# Adafruit_ItsyBitsy_M0.net
KiCad netlist of a schematic drawn in EAGLE
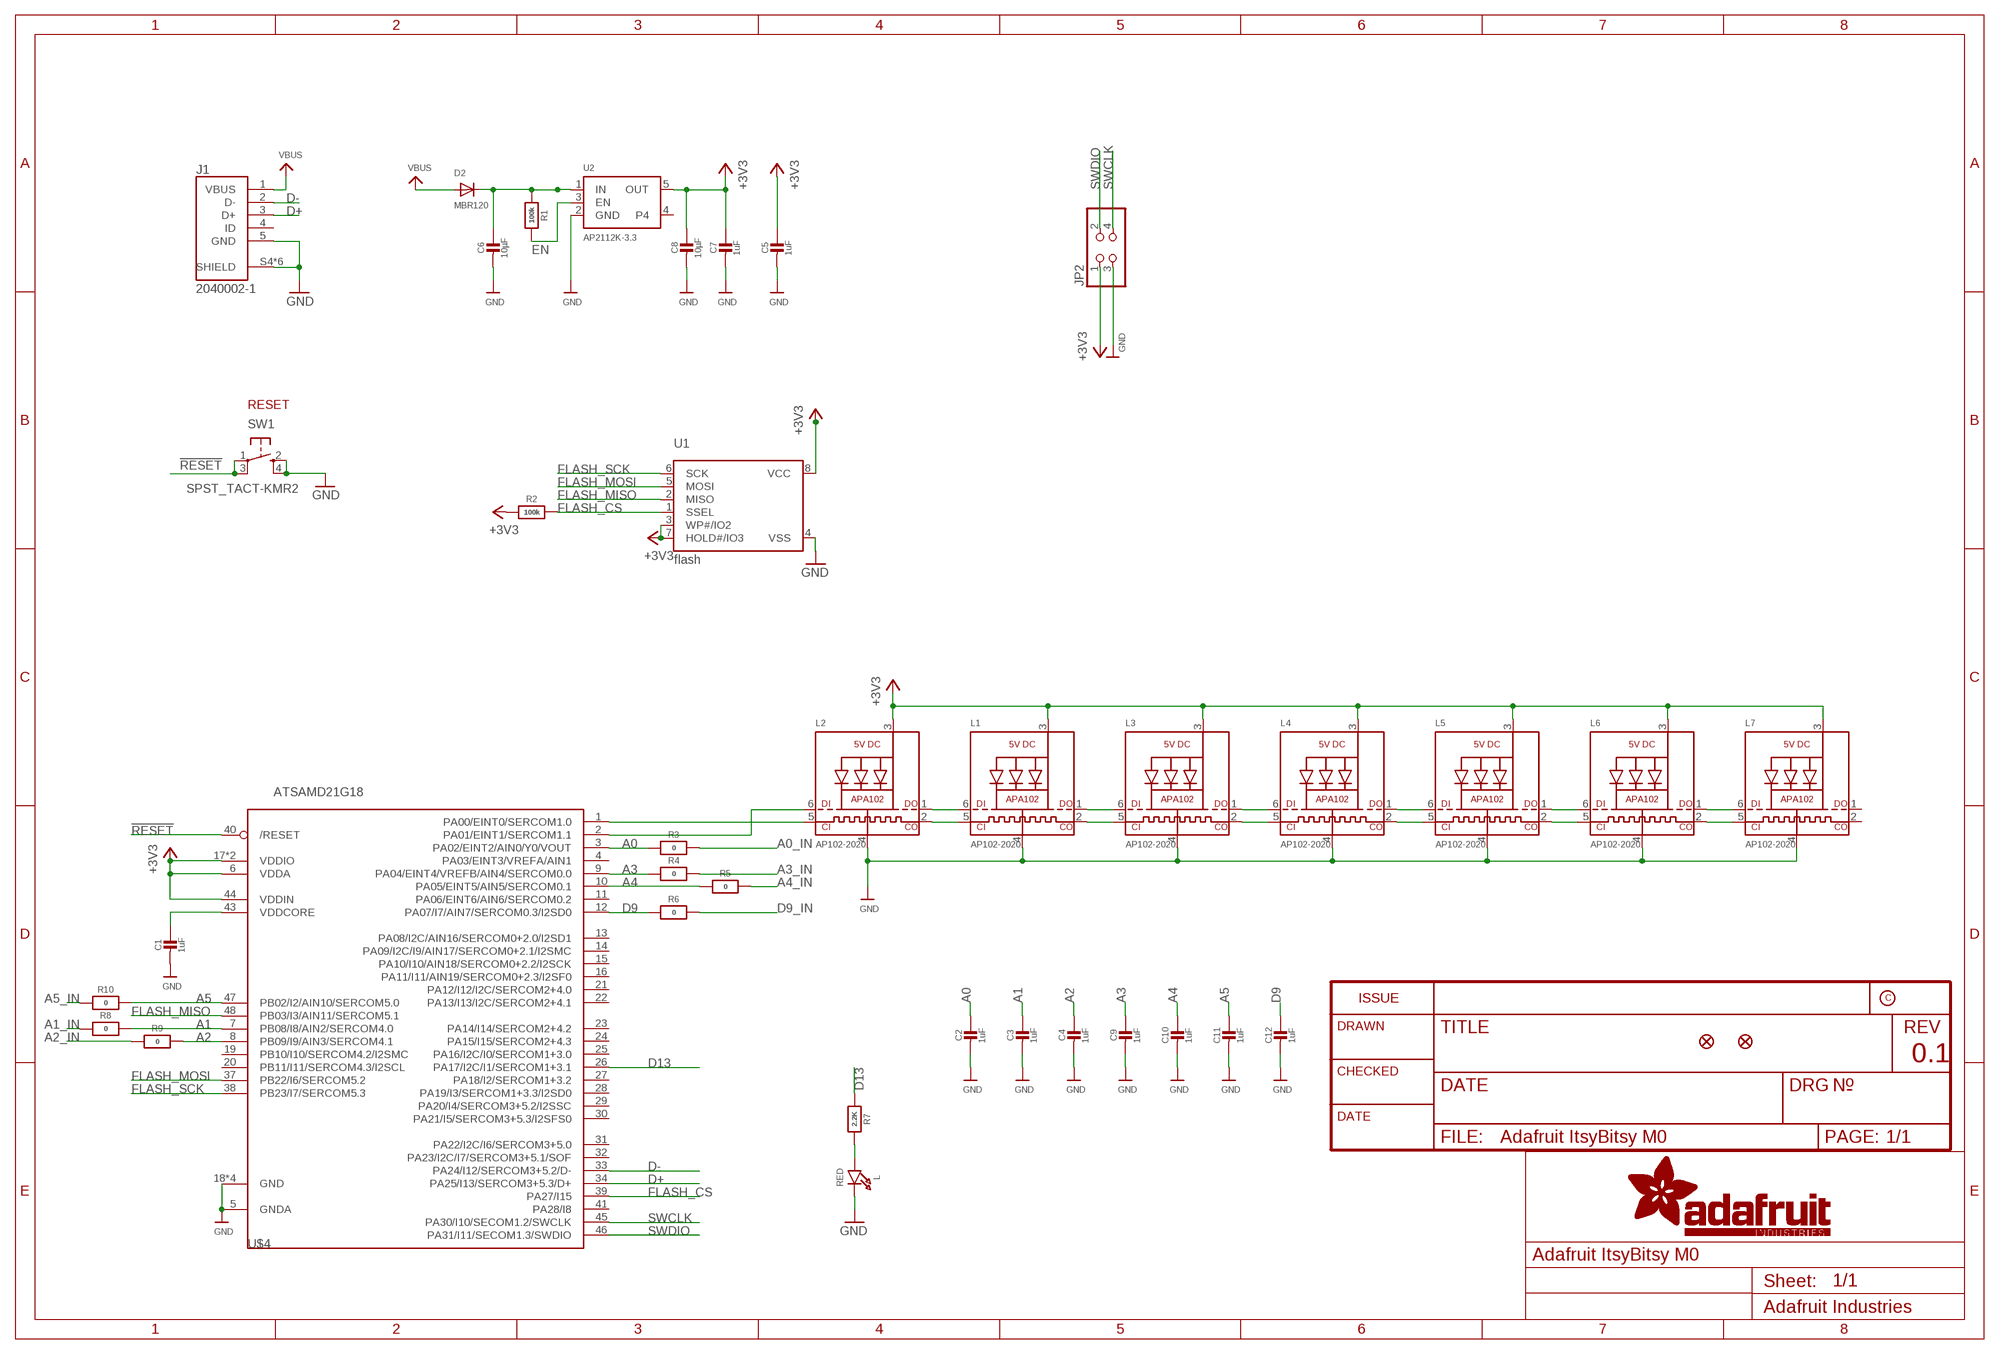
[diagram p0: schematic, sheet 1]

(export (version "E")
  (design (tool "Eeschema 10.0.6"))
  (components
    (comp (ref "C1")
      (value "1uF")
      (footprint "eagle-import:0603-NO")
      (libsource (lib "eagle-import") (part "CAP_CERAMIC0603_NO"))
    )
    (comp (ref "C2")
      (value "1uF")
      (footprint "eagle-import:0603-NO")
      (libsource (lib "eagle-import") (part "CAP_CERAMIC0603_NO"))
    )
    (comp (ref "C3")
      (value "1uF")
      (footprint "eagle-import:0603-NO")
      (libsource (lib "eagle-import") (part "CAP_CERAMIC0603_NO"))
    )
    (comp (ref "C4")
      (value "1uF")
      (footprint "eagle-import:0603-NO")
      (libsource (lib "eagle-import") (part "CAP_CERAMIC0603_NO"))
    )
    (comp (ref "C5")
      (value "1uF")
      (footprint "eagle-import:0603-NO")
      (libsource (lib "eagle-import") (part "CAP_CERAMIC0603_NO"))
    )
    (comp (ref "C6")
      (value "10µF")
      (footprint "eagle-import:0805-NO")
      (libsource (lib "eagle-import") (part "CAP_CERAMIC0805-NOOUTLINE"))
    )
    (comp (ref "C7")
      (value "1uF")
      (footprint "eagle-import:0603-NO")
      (libsource (lib "eagle-import") (part "CAP_CERAMIC0603_NO"))
    )
    (comp (ref "C8")
      (value "10µF")
      (footprint "eagle-import:0805-NO")
      (libsource (lib "eagle-import") (part "CAP_CERAMIC0805-NOOUTLINE"))
    )
    (comp (ref "C9")
      (value "1uF")
      (footprint "eagle-import:0603-NO")
      (libsource (lib "eagle-import") (part "CAP_CERAMIC0603_NO"))
    )
    (comp (ref "C10")
      (value "1uF")
      (footprint "eagle-import:0603-NO")
      (libsource (lib "eagle-import") (part "CAP_CERAMIC0603_NO"))
    )
    (comp (ref "C11")
      (value "1uF")
      (footprint "eagle-import:0603-NO")
      (libsource (lib "eagle-import") (part "CAP_CERAMIC0603_NO"))
    )
    (comp (ref "C12")
      (value "1uF")
      (footprint "eagle-import:0603-NO")
      (libsource (lib "eagle-import") (part "CAP_CERAMIC0603_NO"))
    )
    (comp (ref "D2")
      (value "MBR120")
      (footprint "eagle-import:SOD-123FL")
      (libsource (lib "eagle-import") (part "DIODE_SOD-123FL"))
    )
    (comp (ref "J1")
      (value "2040002-1")
      (footprint "eagle-import:TE_2040002-1")
      (fields (field (name "MF") "TE Connectivity"))
      (libsource (lib "eagle-import") (part "2040002-1"))
    )
    (comp (ref "JP2")
      (value "PINHD-2X2")
      (footprint "eagle-import:2X02")
      (libsource (lib "eagle-import") (part "PINHD-2X2"))
    )
    (comp (ref "L")
      (value "RED")
      (footprint "eagle-import:CHIPLED_0805_NOOUTLINE")
      (libsource (lib "eagle-import") (part "LED0805_NOOUTLINE"))
    )
    (comp (ref "L1")
      (value "AP102-2020")
      (footprint "eagle-import:APA102_2020")
      (libsource (lib "eagle-import") (part "APA1022020"))
    )
    (comp (ref "L2")
      (value "AP102-2020")
      (footprint "eagle-import:APA102_2020")
      (libsource (lib "eagle-import") (part "APA1022020"))
    )
    (comp (ref "L3")
      (value "AP102-2020")
      (footprint "eagle-import:APA102_2020")
      (libsource (lib "eagle-import") (part "APA1022020"))
    )
    (comp (ref "L4")
      (value "AP102-2020")
      (footprint "eagle-import:APA102_2020")
      (libsource (lib "eagle-import") (part "APA1022020"))
    )
    (comp (ref "L5")
      (value "AP102-2020")
      (footprint "eagle-import:APA102_2020")
      (libsource (lib "eagle-import") (part "APA1022020"))
    )
    (comp (ref "L6")
      (value "AP102-2020")
      (footprint "eagle-import:APA102_2020")
      (libsource (lib "eagle-import") (part "APA1022020"))
    )
    (comp (ref "L7")
      (value "AP102-2020")
      (footprint "eagle-import:APA102_2020")
      (libsource (lib "eagle-import") (part "APA1022020"))
    )
    (comp (ref "R1")
      (value "100k")
      (footprint "eagle-import:0603-NO")
      (libsource (lib "eagle-import") (part "RESISTOR_0603_NOOUT"))
    )
    (comp (ref "R2")
      (value "100k")
      (footprint "eagle-import:0603-NO")
      (libsource (lib "eagle-import") (part "RESISTOR_0603_NOOUT"))
    )
    (comp (ref "R3")
      (value "0")
      (footprint "eagle-import:0603-NO")
      (libsource (lib "eagle-import") (part "RESISTOR_0603_NOOUT"))
    )
    (comp (ref "R4")
      (value "0")
      (footprint "eagle-import:0603-NO")
      (libsource (lib "eagle-import") (part "RESISTOR_0603_NOOUT"))
    )
    (comp (ref "R5")
      (value "0")
      (footprint "eagle-import:0603-NO")
      (libsource (lib "eagle-import") (part "RESISTOR_0603_NOOUT"))
    )
    (comp (ref "R6")
      (value "0")
      (footprint "eagle-import:0603-NO")
      (libsource (lib "eagle-import") (part "RESISTOR_0603_NOOUT"))
    )
    (comp (ref "R7")
      (value "2.2K")
      (footprint "eagle-import:0603-NO")
      (libsource (lib "eagle-import") (part "RESISTOR_0603_NOOUT"))
    )
    (comp (ref "R8")
      (value "0")
      (footprint "eagle-import:0603-NO")
      (libsource (lib "eagle-import") (part "RESISTOR_0603_NOOUT"))
    )
    (comp (ref "R9")
      (value "0")
      (footprint "eagle-import:0603-NO")
      (libsource (lib "eagle-import") (part "RESISTOR_0603_NOOUT"))
    )
    (comp (ref "R10")
      (value "0")
      (footprint "eagle-import:0603-NO")
      (libsource (lib "eagle-import") (part "RESISTOR_0603_NOOUT"))
    )
    (comp (ref "SW1")
      (value "SPST_TACT-KMR2")
      (footprint "eagle-import:KMR2")
      (libsource (lib "eagle-import") (part "SPST_TACT-KMR2"))
    )
    (comp (ref "U$4")
      (value "ATSAMD21G18")
      (footprint "eagle-import:TQFN48_7MM")
      (libsource (lib "eagle-import") (part "ATSAMD21G_QFN"))
    )
    (comp (ref "U$34")
      (value "FIDUCIAL_1MM")
      (footprint "eagle-import:FIDUCIAL_1MM")
      (libsource (lib "eagle-import") (part "FIDUCIAL_1MM"))
    )
    (comp (ref "U$35")
      (value "FIDUCIAL_1MM")
      (footprint "eagle-import:FIDUCIAL_1MM")
      (libsource (lib "eagle-import") (part "FIDUCIAL_1MM"))
    )
    (comp (ref "U1")
      (value "flash")
      (footprint "eagle-import:USON8")
      (libsource (lib "eagle-import") (part "SPIFLASH_8PINUX"))
    )
    (comp (ref "U2")
      (value "AP2112K-3.3")
      (footprint "eagle-import:SOT23-5")
      (libsource (lib "eagle-import") (part "VREG_SOT23-5"))
    )
  )
  (nets
    (net (code "1") (name "+3V3") (class "Default")
      (node (ref "C5") (pin "1") (pinfunction "1_1") (pintype "passive"))
      (node (ref "C7") (pin "1") (pinfunction "1_1") (pintype "passive"))
      (node (ref "C8") (pin "1") (pinfunction "1_1") (pintype "passive"))
      (node (ref "JP2") (pin "1") (pinfunction "1_1") (pintype "passive"))
      (node (ref "L1") (pin "3") (pinfunction "VDD_3") (pintype "power_in"))
      (node (ref "L2") (pin "3") (pinfunction "VDD_3") (pintype "power_in"))
      (node (ref "L3") (pin "3") (pinfunction "VDD_3") (pintype "power_in"))
      (node (ref "L4") (pin "3") (pinfunction "VDD_3") (pintype "power_in"))
      (node (ref "L5") (pin "3") (pinfunction "VDD_3") (pintype "power_in"))
      (node (ref "L6") (pin "3") (pinfunction "VDD_3") (pintype "power_in"))
      (node (ref "L7") (pin "3") (pinfunction "VDD_3") (pintype "power_in"))
      (node (ref "R2") (pin "1") (pinfunction "1_1") (pintype "passive"))
      (node (ref "U$4") (pin "17") (pinfunction "VDDIO_17") (pintype "power_in"))
      (node (ref "U$4") (pin "36") (pinfunction "VDDIO_36") (pintype "power_in"))
      (node (ref "U$4") (pin "44") (pinfunction "VDDIN_44") (pintype "power_in"))
      (node (ref "U$4") (pin "6") (pinfunction "VDDA_6") (pintype "power_in"))
      (node (ref "U1") (pin "3") (pinfunction "WP#/IO2_3") (pintype "bidirectional"))
      (node (ref "U1") (pin "7") (pinfunction "HOLD#/IO3_7") (pintype "bidirectional"))
      (node (ref "U1") (pin "8") (pinfunction "VCC_8") (pintype "bidirectional"))
      (node (ref "U2") (pin "5") (pinfunction "OUT_5") (pintype "power_in"))
    )
    (net (code "2") (name "/A0") (class "Default")
      (node (ref "C2") (pin "1") (pinfunction "1_1") (pintype "passive"))
      (node (ref "R3") (pin "1") (pinfunction "1_1") (pintype "passive"))
      (node (ref "U$4") (pin "3") (pinfunction "PA02/EINT2/AIN0/Y0/VOUT_3") (pintype "bidirectional"))
    )
    (net (code "3") (name "/A0_IN") (class "Default")
      (node (ref "R3") (pin "2") (pinfunction "2_2") (pintype "passive"))
    )
    (net (code "4") (name "/A1") (class "Default")
      (node (ref "C3") (pin "1") (pinfunction "1_1") (pintype "passive"))
      (node (ref "R8") (pin "2") (pinfunction "2_2") (pintype "passive"))
      (node (ref "U$4") (pin "7") (pinfunction "PB08/I8/AIN2/SERCOM4.0_7") (pintype "bidirectional"))
    )
    (net (code "5") (name "/A1_IN") (class "Default")
      (node (ref "R8") (pin "1") (pinfunction "1_1") (pintype "passive"))
    )
    (net (code "6") (name "/A2") (class "Default")
      (node (ref "C4") (pin "1") (pinfunction "1_1") (pintype "passive"))
      (node (ref "R9") (pin "2") (pinfunction "2_2") (pintype "passive"))
      (node (ref "U$4") (pin "8") (pinfunction "PB09/I9/AIN3/SERCOM4.1_8") (pintype "bidirectional"))
    )
    (net (code "7") (name "/A2_IN") (class "Default")
      (node (ref "R9") (pin "1") (pinfunction "1_1") (pintype "passive"))
    )
    (net (code "8") (name "/A3") (class "Default")
      (node (ref "C9") (pin "1") (pinfunction "1_1") (pintype "passive"))
      (node (ref "R4") (pin "1") (pinfunction "1_1") (pintype "passive"))
      (node (ref "U$4") (pin "9") (pinfunction "PA04/EINT4/VREFB/AIN4/SERCOM0.0_9") (pintype "bidirectional"))
    )
    (net (code "9") (name "/A3_IN") (class "Default")
      (node (ref "R4") (pin "2") (pinfunction "2_2") (pintype "passive"))
    )
    (net (code "10") (name "/A4") (class "Default")
      (node (ref "C10") (pin "1") (pinfunction "1_1") (pintype "passive"))
      (node (ref "R5") (pin "1") (pinfunction "1_1") (pintype "passive"))
      (node (ref "U$4") (pin "10") (pinfunction "PA05/EINT5/AIN5/SERCOM0.1_10") (pintype "bidirectional"))
    )
    (net (code "11") (name "/A4_IN") (class "Default")
      (node (ref "R5") (pin "2") (pinfunction "2_2") (pintype "passive"))
    )
    (net (code "12") (name "/A5") (class "Default")
      (node (ref "C11") (pin "1") (pinfunction "1_1") (pintype "passive"))
      (node (ref "R10") (pin "2") (pinfunction "2_2") (pintype "passive"))
      (node (ref "U$4") (pin "47") (pinfunction "PB02/I2/AIN10/SERCOM5.0_47") (pintype "bidirectional"))
    )
    (net (code "13") (name "/A5_IN") (class "Default")
      (node (ref "R10") (pin "1") (pinfunction "1_1") (pintype "passive"))
    )
    (net (code "14") (name "/D+") (class "Default")
      (node (ref "J1") (pin "3") (pinfunction "D+_3") (pintype "bidirectional"))
      (node (ref "U$4") (pin "34") (pinfunction "PA25/I13/SERCOM3+5.3/D+_34") (pintype "bidirectional"))
    )
    (net (code "15") (name "/D-") (class "Default")
      (node (ref "J1") (pin "2") (pinfunction "D-_2") (pintype "bidirectional"))
      (node (ref "U$4") (pin "33") (pinfunction "PA24/I12/SERCOM3+5.2/D-_33") (pintype "bidirectional"))
    )
    (net (code "16") (name "/D9") (class "Default")
      (node (ref "C12") (pin "1") (pinfunction "1_1") (pintype "passive"))
      (node (ref "R6") (pin "1") (pinfunction "1_1") (pintype "passive"))
      (node (ref "U$4") (pin "12") (pinfunction "PA07/I7/AIN7/SERCOM0.3/I2SD0_12") (pintype "bidirectional"))
    )
    (net (code "17") (name "/D9_IN") (class "Default")
      (node (ref "R6") (pin "2") (pinfunction "2_2") (pintype "passive"))
    )
    (net (code "18") (name "/D13") (class "Default")
      (node (ref "R7") (pin "1") (pinfunction "1_1") (pintype "passive"))
      (node (ref "U$4") (pin "26") (pinfunction "PA17/I2C/I1/SERCOM1+3.1_26") (pintype "bidirectional"))
    )
    (net (code "19") (name "/EN") (class "Default")
      (node (ref "R1") (pin "2") (pinfunction "2_2") (pintype "passive"))
      (node (ref "U2") (pin "3") (pinfunction "EN_3") (pintype "input"))
    )
    (net (code "20") (name "/FLASH_CS") (class "Default")
      (node (ref "R2") (pin "2") (pinfunction "2_2") (pintype "passive"))
      (node (ref "U$4") (pin "39") (pinfunction "PA27/I15_39") (pintype "bidirectional"))
      (node (ref "U1") (pin "1") (pinfunction "SSEL_1") (pintype "bidirectional"))
    )
    (net (code "21") (name "/FLASH_MISO") (class "Default")
      (node (ref "U$4") (pin "48") (pinfunction "PB03/I3/AIN11/SERCOM5.1_48") (pintype "bidirectional"))
      (node (ref "U1") (pin "2") (pinfunction "MISO_2") (pintype "bidirectional"))
    )
    (net (code "22") (name "/FLASH_MOSI") (class "Default")
      (node (ref "U$4") (pin "37") (pinfunction "PB22/I6/SERCOM5.2_37") (pintype "bidirectional"))
      (node (ref "U1") (pin "5") (pinfunction "MOSI_5") (pintype "bidirectional"))
    )
    (net (code "23") (name "/FLASH_SCK") (class "Default")
      (node (ref "U$4") (pin "38") (pinfunction "PB23/I7/SERCOM5.3_38") (pintype "bidirectional"))
      (node (ref "U1") (pin "6") (pinfunction "SCK_6") (pintype "bidirectional"))
    )
    (net (code "24") (name "/SWCLK") (class "Default")
      (node (ref "JP2") (pin "4") (pinfunction "4_4") (pintype "passive"))
      (node (ref "U$4") (pin "45") (pinfunction "PA30/I10/SECOM1.2/SWCLK_45") (pintype "bidirectional"))
    )
    (net (code "25") (name "/SWDIO") (class "Default")
      (node (ref "JP2") (pin "2") (pinfunction "2_2") (pintype "passive"))
      (node (ref "U$4") (pin "46") (pinfunction "PA31/I11/SECOM1.3/SWDIO_46") (pintype "bidirectional"))
    )
    (net (code "26") (name "/~{RESET}") (class "Default")
      (node (ref "SW1") (pin "1") (pinfunction "P_1") (pintype "passive"))
      (node (ref "SW1") (pin "3") (pinfunction "P1_3") (pintype "passive"))
      (node (ref "U$4") (pin "40") (pinfunction "/RESET_40") (pintype "bidirectional"))
    )
    (net (code "27") (name "GND") (class "Default")
      (node (ref "C1") (pin "2") (pinfunction "2_2") (pintype "passive"))
      (node (ref "C10") (pin "2") (pinfunction "2_2") (pintype "passive"))
      (node (ref "C11") (pin "2") (pinfunction "2_2") (pintype "passive"))
      (node (ref "C12") (pin "2") (pinfunction "2_2") (pintype "passive"))
      (node (ref "C2") (pin "2") (pinfunction "2_2") (pintype "passive"))
      (node (ref "C3") (pin "2") (pinfunction "2_2") (pintype "passive"))
      (node (ref "C4") (pin "2") (pinfunction "2_2") (pintype "passive"))
      (node (ref "C5") (pin "2") (pinfunction "2_2") (pintype "passive"))
      (node (ref "C6") (pin "2") (pinfunction "2_2") (pintype "passive"))
      (node (ref "C7") (pin "2") (pinfunction "2_2") (pintype "passive"))
      (node (ref "C8") (pin "2") (pinfunction "2_2") (pintype "passive"))
      (node (ref "C9") (pin "2") (pinfunction "2_2") (pintype "passive"))
      (node (ref "J1") (pin "5") (pinfunction "GND_5") (pintype "power_in"))
      (node (ref "J1") (pin "S4") (pinfunction "SHIELD_S4") (pintype "power_in"))
      (node (ref "J1") (pin "S5") (pinfunction "SHIELD_S5") (pintype "power_in"))
      (node (ref "J1") (pin "SH1") (pinfunction "SHIELD_SH1") (pintype "power_in"))
      (node (ref "J1") (pin "SH2") (pinfunction "SHIELD_SH2") (pintype "power_in"))
      (node (ref "J1") (pin "SH3") (pinfunction "SHIELD_SH3") (pintype "power_in"))
      (node (ref "J1") (pin "SH4") (pinfunction "SHIELD_SH4") (pintype "power_in"))
      (node (ref "JP2") (pin "3") (pinfunction "3_3") (pintype "passive"))
      (node (ref "L") (pin "C") (pinfunction "C_C") (pintype "passive"))
      (node (ref "L1") (pin "4") (pinfunction "GND_4") (pintype "power_in"))
      (node (ref "L2") (pin "4") (pinfunction "GND_4") (pintype "power_in"))
      (node (ref "L3") (pin "4") (pinfunction "GND_4") (pintype "power_in"))
      (node (ref "L4") (pin "4") (pinfunction "GND_4") (pintype "power_in"))
      (node (ref "L5") (pin "4") (pinfunction "GND_4") (pintype "power_in"))
      (node (ref "L6") (pin "4") (pinfunction "GND_4") (pintype "power_in"))
      (node (ref "L7") (pin "4") (pinfunction "GND_4") (pintype "power_in"))
      (node (ref "SW1") (pin "2") (pinfunction "S_2") (pintype "passive"))
      (node (ref "SW1") (pin "4") (pinfunction "S1_4") (pintype "passive"))
      (node (ref "U$4") (pin "18") (pinfunction "GND_18") (pintype "power_in"))
      (node (ref "U$4") (pin "35") (pinfunction "GND_35") (pintype "power_in"))
      (node (ref "U$4") (pin "42") (pinfunction "GND_42") (pintype "power_in"))
      (node (ref "U$4") (pin "5") (pinfunction "GNDA_5") (pintype "power_in"))
      (node (ref "U$4") (pin "THERMAL") (pinfunction "GND_THERMAL") (pintype "power_in"))
      (node (ref "U1") (pin "4") (pinfunction "VSS_4") (pintype "bidirectional"))
      (node (ref "U2") (pin "2") (pinfunction "GND_2") (pintype "power_in"))
    )
    (net (code "28") (name "Net-(L-PadA)") (class "Default")
      (node (ref "L") (pin "A") (pinfunction "A_A") (pintype "passive"))
      (node (ref "R7") (pin "2") (pinfunction "2_2") (pintype "passive"))
    )
    (net (code "29") (name "Net-(L1-CKI)") (class "Default")
      (node (ref "L1") (pin "5") (pinfunction "CKI_5") (pintype "input"))
      (node (ref "L2") (pin "2") (pinfunction "CKO_2") (pintype "output"))
    )
    (net (code "30") (name "Net-(L1-CKO)") (class "Default")
      (node (ref "L1") (pin "2") (pinfunction "CKO_2") (pintype "output"))
      (node (ref "L3") (pin "5") (pinfunction "CKI_5") (pintype "input"))
    )
    (net (code "31") (name "Net-(L1-DI)") (class "Default")
      (node (ref "L1") (pin "6") (pinfunction "DI_6") (pintype "input"))
      (node (ref "L2") (pin "1") (pinfunction "DO_1") (pintype "output"))
    )
    (net (code "32") (name "Net-(L1-DO)") (class "Default")
      (node (ref "L1") (pin "1") (pinfunction "DO_1") (pintype "output"))
      (node (ref "L3") (pin "6") (pinfunction "DI_6") (pintype "input"))
    )
    (net (code "33") (name "Net-(L2-CKI)") (class "Default")
      (node (ref "L2") (pin "5") (pinfunction "CKI_5") (pintype "input"))
      (node (ref "U$4") (pin "1") (pinfunction "PA00/EINT0/SERCOM1.0_1") (pintype "bidirectional"))
    )
    (net (code "34") (name "Net-(L2-DI)") (class "Default")
      (node (ref "L2") (pin "6") (pinfunction "DI_6") (pintype "input"))
      (node (ref "U$4") (pin "2") (pinfunction "PA01/EINT1/SERCOM1.1_2") (pintype "bidirectional"))
    )
    (net (code "35") (name "Net-(L3-CKO)") (class "Default")
      (node (ref "L3") (pin "2") (pinfunction "CKO_2") (pintype "output"))
      (node (ref "L4") (pin "5") (pinfunction "CKI_5") (pintype "input"))
    )
    (net (code "36") (name "Net-(L3-DO)") (class "Default")
      (node (ref "L3") (pin "1") (pinfunction "DO_1") (pintype "output"))
      (node (ref "L4") (pin "6") (pinfunction "DI_6") (pintype "input"))
    )
    (net (code "37") (name "Net-(L4-CKO)") (class "Default")
      (node (ref "L4") (pin "2") (pinfunction "CKO_2") (pintype "output"))
      (node (ref "L5") (pin "5") (pinfunction "CKI_5") (pintype "input"))
    )
    (net (code "38") (name "Net-(L4-DO)") (class "Default")
      (node (ref "L4") (pin "1") (pinfunction "DO_1") (pintype "output"))
      (node (ref "L5") (pin "6") (pinfunction "DI_6") (pintype "input"))
    )
    (net (code "39") (name "Net-(L5-CKO)") (class "Default")
      (node (ref "L5") (pin "2") (pinfunction "CKO_2") (pintype "output"))
      (node (ref "L6") (pin "5") (pinfunction "CKI_5") (pintype "input"))
    )
    (net (code "40") (name "Net-(L5-DO)") (class "Default")
      (node (ref "L5") (pin "1") (pinfunction "DO_1") (pintype "output"))
      (node (ref "L6") (pin "6") (pinfunction "DI_6") (pintype "input"))
    )
    (net (code "41") (name "Net-(L6-CKO)") (class "Default")
      (node (ref "L6") (pin "2") (pinfunction "CKO_2") (pintype "output"))
      (node (ref "L7") (pin "5") (pinfunction "CKI_5") (pintype "input"))
    )
    (net (code "42") (name "Net-(L6-DO)") (class "Default")
      (node (ref "L6") (pin "1") (pinfunction "DO_1") (pintype "output"))
      (node (ref "L7") (pin "6") (pinfunction "DI_6") (pintype "input"))
    )
    (net (code "43") (name "Net-(U$4-VDDCORE)") (class "Default")
      (node (ref "C1") (pin "1") (pinfunction "1_1") (pintype "passive"))
      (node (ref "U$4") (pin "43") (pinfunction "VDDCORE_43") (pintype "power_in"))
    )
    (net (code "44") (name "Net-(U2-IN)") (class "Default")
      (node (ref "C6") (pin "1") (pinfunction "1_1") (pintype "passive"))
      (node (ref "D2") (pin "C") (pinfunction "C_C") (pintype "passive"))
      (node (ref "R1") (pin "1") (pinfunction "1_1") (pintype "passive"))
      (node (ref "U2") (pin "1") (pinfunction "IN_1") (pintype "power_in"))
    )
    (net (code "45") (name "VBUS") (class "Default")
      (node (ref "D2") (pin "A") (pinfunction "A_A") (pintype "passive"))
      (node (ref "J1") (pin "1") (pinfunction "VBUS_1") (pintype "power_in"))
    )
    (net (code "46") (name "unconnected-(J1-ID-Pad4)") (class "Default")
      (node (ref "J1") (pin "4") (pinfunction "ID_4") (pintype "bidirectional"))
    )
    (net (code "47") (name "unconnected-(L7-CKO-Pad2)") (class "Default")
      (node (ref "L7") (pin "2") (pinfunction "CKO_2") (pintype "output"))
    )
    (net (code "48") (name "unconnected-(L7-DO-Pad1)") (class "Default")
      (node (ref "L7") (pin "1") (pinfunction "DO_1") (pintype "output"))
    )
    (net (code "49") (name "unconnected-(U$4-PA03{slash}EINT3{slash}VREFA{slash}AIN1-Pad4)") (class "Default")
      (node (ref "U$4") (pin "4") (pinfunction "PA03/EINT3/VREFA/AIN1_4") (pintype "bidirectional"))
    )
    (net (code "50") (name "unconnected-(U$4-PA06{slash}EINT6{slash}AIN6{slash}SERCOM0.2-Pad11)") (class "Default")
      (node (ref "U$4") (pin "11") (pinfunction "PA06/EINT6/AIN6/SERCOM0.2_11") (pintype "bidirectional"))
    )
    (net (code "51") (name "unconnected-(U$4-PA08{slash}I2C{slash}AIN16{slash}SERCOM0+2.0{slash}I2SD1-Pad13)") (class "Default")
      (node (ref "U$4") (pin "13") (pinfunction "PA08/I2C/AIN16/SERCOM0+2.0/I2SD1_13") (pintype "bidirectional"))
    )
    (net (code "52") (name "unconnected-(U$4-PA09{slash}I2C{slash}I9{slash}AIN17{slash}SERCOM0+2.1{slash}I2SMC-Pad14)") (class "Default")
      (node (ref "U$4") (pin "14") (pinfunction "PA09/I2C/I9/AIN17/SERCOM0+2.1/I2SMC_14") (pintype "bidirectional"))
    )
    (net (code "53") (name "unconnected-(U$4-PA10{slash}I10{slash}AIN18{slash}SERCOM0+2.2{slash}I2SCK-Pad15)") (class "Default")
      (node (ref "U$4") (pin "15") (pinfunction "PA10/I10/AIN18/SERCOM0+2.2/I2SCK_15") (pintype "bidirectional"))
    )
    (net (code "54") (name "unconnected-(U$4-PA11{slash}I11{slash}AIN19{slash}SERCOM0+2.3{slash}I2SF0-Pad16)") (class "Default")
      (node (ref "U$4") (pin "16") (pinfunction "PA11/I11/AIN19/SERCOM0+2.3/I2SF0_16") (pintype "bidirectional"))
    )
    (net (code "55") (name "unconnected-(U$4-PA12{slash}I12{slash}I2C{slash}SERCOM2+4.0-Pad21)") (class "Default")
      (node (ref "U$4") (pin "21") (pinfunction "PA12/I12/I2C/SERCOM2+4.0_21") (pintype "bidirectional"))
    )
    (net (code "56") (name "unconnected-(U$4-PA13{slash}I13{slash}I2C{slash}SERCOM2+4.1-Pad22)") (class "Default")
      (node (ref "U$4") (pin "22") (pinfunction "PA13/I13/I2C/SERCOM2+4.1_22") (pintype "bidirectional"))
    )
    (net (code "57") (name "unconnected-(U$4-PA14{slash}I14{slash}SERCOM2+4.2-Pad23)") (class "Default")
      (node (ref "U$4") (pin "23") (pinfunction "PA14/I14/SERCOM2+4.2_23") (pintype "bidirectional"))
    )
    (net (code "58") (name "unconnected-(U$4-PA15{slash}I15{slash}SERCOM2+4.3-Pad24)") (class "Default")
      (node (ref "U$4") (pin "24") (pinfunction "PA15/I15/SERCOM2+4.3_24") (pintype "bidirectional"))
    )
    (net (code "59") (name "unconnected-(U$4-PA16{slash}I2C{slash}I0{slash}SERCOM1+3.0-Pad25)") (class "Default")
      (node (ref "U$4") (pin "25") (pinfunction "PA16/I2C/I0/SERCOM1+3.0_25") (pintype "bidirectional"))
    )
    (net (code "60") (name "unconnected-(U$4-PA18{slash}I2{slash}SERCOM1+3.2-Pad27)") (class "Default")
      (node (ref "U$4") (pin "27") (pinfunction "PA18/I2/SERCOM1+3.2_27") (pintype "bidirectional"))
    )
    (net (code "61") (name "unconnected-(U$4-PA19{slash}I3{slash}SERCOM1+3.3{slash}I2SD0-Pad28)") (class "Default")
      (node (ref "U$4") (pin "28") (pinfunction "PA19/I3/SERCOM1+3.3/I2SD0_28") (pintype "bidirectional"))
    )
    (net (code "62") (name "unconnected-(U$4-PA20{slash}I4{slash}SERCOM3+5.2{slash}I2SSC-Pad29)") (class "Default")
      (node (ref "U$4") (pin "29") (pinfunction "PA20/I4/SERCOM3+5.2/I2SSC_29") (pintype "bidirectional"))
    )
    (net (code "63") (name "unconnected-(U$4-PA21{slash}I5{slash}SERCOM3+5.3{slash}I2SFS0-Pad30)") (class "Default")
      (node (ref "U$4") (pin "30") (pinfunction "PA21/I5/SERCOM3+5.3/I2SFS0_30") (pintype "bidirectional"))
    )
    (net (code "64") (name "unconnected-(U$4-PA22{slash}I2C{slash}I6{slash}SERCOM3+5.0-Pad31)") (class "Default")
      (node (ref "U$4") (pin "31") (pinfunction "PA22/I2C/I6/SERCOM3+5.0_31") (pintype "bidirectional"))
    )
    (net (code "65") (name "unconnected-(U$4-PA23{slash}I2C{slash}I7{slash}SERCOM3+5.1{slash}SOF-Pad32)") (class "Default")
      (node (ref "U$4") (pin "32") (pinfunction "PA23/I2C/I7/SERCOM3+5.1/SOF_32") (pintype "bidirectional"))
    )
    (net (code "66") (name "unconnected-(U$4-PA28{slash}I8-Pad41)") (class "Default")
      (node (ref "U$4") (pin "41") (pinfunction "PA28/I8_41") (pintype "bidirectional"))
    )
    (net (code "67") (name "unconnected-(U$4-PB10{slash}I10{slash}SERCOM4.2{slash}I2SMC-Pad19)") (class "Default")
      (node (ref "U$4") (pin "19") (pinfunction "PB10/I10/SERCOM4.2/I2SMC_19") (pintype "bidirectional"))
    )
    (net (code "68") (name "unconnected-(U$4-PB11{slash}I11{slash}SERCOM4.3{slash}I2SCL-Pad20)") (class "Default")
      (node (ref "U$4") (pin "20") (pinfunction "PB11/I11/SERCOM4.3/I2SCL_20") (pintype "bidirectional"))
    )
    (net (code "69") (name "unconnected-(U2-P4-Pad4)") (class "Default")
      (node (ref "U2") (pin "4") (pinfunction "P4_4") (pintype "bidirectional"))
    )
  )
)
